# shoff400.net
KiCad netlist of a schematic drawn in EAGLE
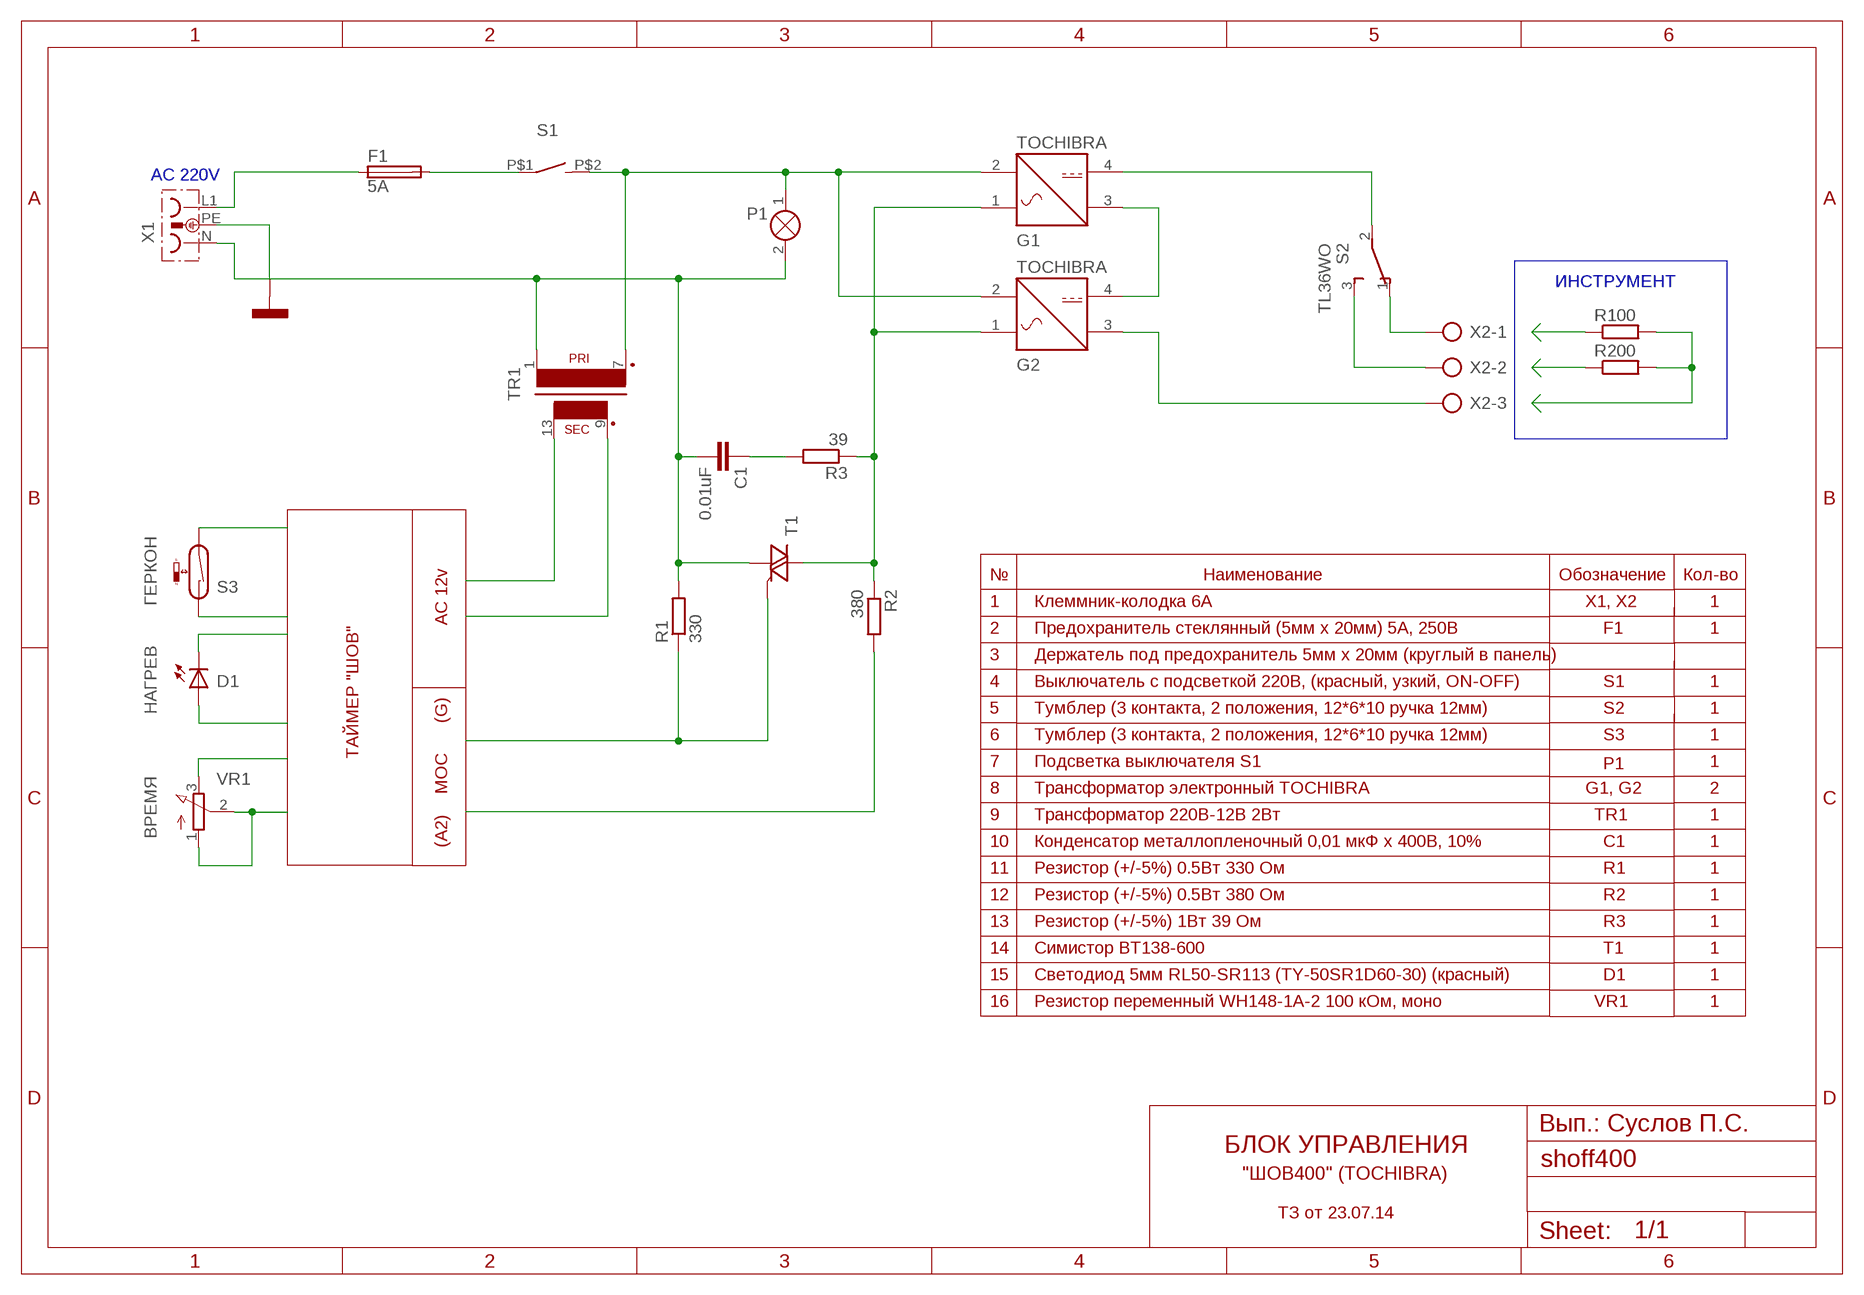
[diagram p0: schematic, sheet 1]

(export (version "E")
  (design (tool "Eeschema 10.0.6"))
  (components
    (comp (ref "C1")
      (value "0.01uF")
      (footprint "eagle-import:C025-030X050")
      (libsource (lib "eagle-import") (part "C-EU025-030X050"))
    )
    (comp (ref "F1")
      (value "5A")
      (footprint "eagle-import:GSH15")
      (fields (field (name "MPN") "64900001039"))
      (libsource (lib "eagle-import") (part "GSH15"))
    )
    (comp (ref "G1")
      (value "TOCHIBRA")
      (footprint "eagle-import:NETZTEIL_GLEICHSPANNUNG")
      (libsource (lib "eagle-import") (part "NETZTEIL_GLEICHSPANNUNG"))
    )
    (comp (ref "G2")
      (value "TOCHIBRA")
      (footprint "eagle-import:NETZTEIL_GLEICHSPANNUNG")
      (libsource (lib "eagle-import") (part "NETZTEIL_GLEICHSPANNUNG"))
    )
    (comp (ref "GG")
      (value "MASSE_ALLGEMEIN")
      (footprint "eagle-import:MASSE_ALLGEMEIN")
      (libsource (lib "eagle-import") (part "MASSE_ALLGEMEIN"))
    )
    (comp (ref "P1")
      (value "SIGNALLAMPE")
      (footprint "eagle-import:LAMPE")
      (libsource (lib "eagle-import") (part "SIGNALLAMPE"))
    )
    (comp (ref "R1")
      (value "330")
      (footprint "eagle-import:0207_5V")
      (libsource (lib "eagle-import") (part "R-EU_0207/5V"))
    )
    (comp (ref "R2")
      (value "380")
      (footprint "eagle-import:0207_5V")
      (libsource (lib "eagle-import") (part "R-EU_0207/5V"))
    )
    (comp (ref "R3")
      (value "39")
      (footprint "eagle-import:0207_5V")
      (libsource (lib "eagle-import") (part "R-EU_0207/5V"))
    )
    (comp (ref "R100")
      (value "R-EU_R0201")
      (footprint "eagle-import:R0201")
      (libsource (lib "eagle-import") (part "R-EU_R0201"))
    )
    (comp (ref "R200")
      (value "R-EU_R0201")
      (footprint "eagle-import:R0201")
      (libsource (lib "eagle-import") (part "R-EU_R0201"))
    )
    (comp (ref "S1")
      (value "SCHLIESSER_ARBEITSKONTAKT")
      (footprint "eagle-import:1")
      (libsource (lib "eagle-import") (part "SCHLIESSER_ARBEITSKONTAKT"))
    )
    (comp (ref "S2")
      (value "TL36WO")
      (footprint "eagle-import:TL3XWO")
      (libsource (lib "eagle-import") (part "TL36WO"))
    )
    (comp (ref "S3")
      (value "ГЕРКОН")
      (footprint "eagle-import:CT10-G1")
      (fields (field (name "MF") "COTO TECHNOLOGY") (field (name "MPN") "CT10-1530-G1"))
      (libsource (lib "eagle-import") (part "REED-SWITCH-CT10-1530-G1"))
    )
    (comp (ref "T1")
      (value "BTA26-V")
      (footprint "eagle-import:TOP3S-1")
      (libsource (lib "eagle-import") (part "BTA26-V"))
    )
    (comp (ref "TR1")
      (value "BV054-5381.0K")
      (footprint "eagle-import:EI54-18,8_16VA")
      (libsource (lib "eagle-import") (part "BV054-5381.0K"))
    )
    (comp (ref "X1")
      (value "STECKDOSE")
      (footprint "eagle-import:STECKDOSE")
      (libsource (lib "eagle-import") (part "STECKDOSE"))
    )
    (comp (ref "X2")
      (value "AK500/3")
      (footprint "eagle-import:AK500_3")
      (libsource (lib "eagle-import") (part "AK500/3"))
    )
    (comp (ref "ВРЕМЯ")
      (value "3RP/1610N")
      (footprint "eagle-import:3RP_1610N")
      (libsource (lib "eagle-import") (part "3RP/1610N"))
    )
    (comp (ref "ГОТОВ")
      (value "НАГРЕВ")
      (footprint "eagle-import:LED5MM")
      (libsource (lib "eagle-import") (part "LED5MM"))
    )
  )
  (nets
    (net (code "1") (name "Net-(C1-Pad1)") (class "Default")
      (node (ref "C1") (pin "1") (pinfunction "1_1") (pintype "passive"))
      (node (ref "R3") (pin "2") (pinfunction "2_2") (pintype "passive"))
    )
    (net (code "2") (name "Net-(F1-Pad1)") (class "Default")
      (node (ref "F1") (pin "1") (pinfunction "1_1") (pintype "passive"))
      (node (ref "X1") (pin "L1") (pinfunction "L1_L1") (pintype "passive"))
    )
    (net (code "3") (name "Net-(G1-Pad1)") (class "Default")
      (node (ref "G1") (pin "1") (pinfunction "1_1") (pintype "passive"))
      (node (ref "G2") (pin "1") (pinfunction "1_1") (pintype "passive"))
      (node (ref "R2") (pin "1") (pinfunction "1_1") (pintype "passive"))
      (node (ref "R3") (pin "1") (pinfunction "1_1") (pintype "passive"))
      (node (ref "T1") (pin "A2") (pinfunction "A2_A2") (pintype "passive"))
    )
    (net (code "4") (name "Net-(G1-Pad3)") (class "Default")
      (node (ref "G1") (pin "3") (pinfunction "3_3") (pintype "passive"))
      (node (ref "G2") (pin "4") (pinfunction "4_4") (pintype "passive"))
    )
    (net (code "5") (name "Net-(GG-0V)") (class "Default")
      (node (ref "GG") (pin "1") (pinfunction "0V_1") (pintype "passive"))
      (node (ref "X1") (pin "PE") (pinfunction "PE_PE") (pintype "passive"))
    )
    (net (code "6") (name "Net-(P1-X1)") (class "Default")
      (node (ref "G1") (pin "2") (pinfunction "2_2") (pintype "passive"))
      (node (ref "G2") (pin "2") (pinfunction "2_2") (pintype "passive"))
      (node (ref "P1") (pin "1") (pinfunction "X1_1") (pintype "passive"))
      (node (ref "S1") (pin "P$2") (pinfunction "3_P$2") (pintype "passive"))
      (node (ref "TR1") (pin "7") (pinfunction "P2_7") (pintype "passive"))
    )
    (net (code "7") (name "Net-(P1-X2)") (class "Default")
      (node (ref "C1") (pin "2") (pinfunction "2_2") (pintype "passive"))
      (node (ref "P1") (pin "2") (pinfunction "X2_2") (pintype "passive"))
      (node (ref "R1") (pin "2") (pinfunction "2_2") (pintype "passive"))
      (node (ref "T1") (pin "A1") (pinfunction "A1_A1") (pintype "passive"))
      (node (ref "TR1") (pin "1") (pinfunction "P1_1") (pintype "passive"))
      (node (ref "X1") (pin "N") (pinfunction "N_N") (pintype "passive"))
    )
    (net (code "8") (name "Net-(R1-Pad1)") (class "Default")
      (node (ref "R1") (pin "1") (pinfunction "1_1") (pintype "passive"))
      (node (ref "T1") (pin "G") (pinfunction "G_G") (pintype "passive"))
    )
    (net (code "9") (name "Net-(R100-Pad2)") (class "Default")
      (node (ref "R100") (pin "2") (pinfunction "2_2") (pintype "passive"))
      (node (ref "R200") (pin "2") (pinfunction "2_2") (pintype "passive"))
    )
    (net (code "10") (name "Net-(S1-4)") (class "Default")
      (node (ref "F1") (pin "2") (pinfunction "2_2") (pintype "passive"))
      (node (ref "S1") (pin "P$1") (pinfunction "4_P$1") (pintype "passive"))
    )
    (net (code "11") (name "Net-(S2-O)") (class "Default")
      (node (ref "S2") (pin "1") (pinfunction "O_1") (pintype "passive"))
      (node (ref "X2") (pin "1") (pinfunction "KL_1") (pintype "passive"))
    )
    (net (code "12") (name "Net-(S2-P)") (class "Default")
      (node (ref "G1") (pin "4") (pinfunction "4_4") (pintype "passive"))
      (node (ref "S2") (pin "2") (pinfunction "P_2") (pintype "passive"))
    )
    (net (code "13") (name "Net-(S2-S)") (class "Default")
      (node (ref "S2") (pin "3") (pinfunction "S_3") (pintype "passive"))
      (node (ref "X2") (pin "2") (pinfunction "KL_2") (pintype "passive"))
    )
    (net (code "14") (name "Net-(X2C-KL)") (class "Default")
      (node (ref "G2") (pin "3") (pinfunction "3_3") (pintype "passive"))
      (node (ref "X2") (pin "3") (pinfunction "KL_3") (pintype "passive"))
    )
    (net (code "15") (name "Net-(ВРЕМЯ-A)") (class "Default")
      (node (ref "ВРЕМЯ") (pin "1") (pinfunction "A_1") (pintype "passive"))
      (node (ref "ВРЕМЯ") (pin "2") (pinfunction "S_2") (pintype "passive"))
    )
    (net (code "16") (name "unconnected-(R2-Pad2)") (class "Default")
      (node (ref "R2") (pin "2") (pinfunction "2_2") (pintype "passive"))
    )
    (net (code "17") (name "unconnected-(R100-Pad1)") (class "Default")
      (node (ref "R100") (pin "1") (pinfunction "1_1") (pintype "passive"))
    )
    (net (code "18") (name "unconnected-(R200-Pad1)") (class "Default")
      (node (ref "R200") (pin "1") (pinfunction "1_1") (pintype "passive"))
    )
    (net (code "19") (name "unconnected-(S3-Pad1)") (class "Default")
      (node (ref "S3") (pin "1") (pinfunction "1_1") (pintype "passive"))
    )
    (net (code "20") (name "unconnected-(S3-Pad2)") (class "Default")
      (node (ref "S3") (pin "2") (pinfunction "2_2") (pintype "passive"))
    )
    (net (code "21") (name "unconnected-(TR1-S3-Pad9)") (class "Default")
      (node (ref "TR1") (pin "9") (pinfunction "S3_9") (pintype "passive"))
    )
    (net (code "22") (name "unconnected-(TR1-S4-Pad13)") (class "Default")
      (node (ref "TR1") (pin "13") (pinfunction "S4_13") (pintype "passive"))
    )
    (net (code "23") (name "unconnected-(ВРЕМЯ-E-Pad3)") (class "Default")
      (node (ref "ВРЕМЯ") (pin "3") (pinfunction "E_3") (pintype "passive"))
    )
    (net (code "24") (name "unconnected-(ГОТОВ-C-PadK)") (class "Default")
      (node (ref "ГОТОВ") (pin "K") (pinfunction "C_K") (pintype "passive"))
    )
    (net (code "25") (name "unconnected-(ГОТОВ-PadA)") (class "Default")
      (node (ref "ГОТОВ") (pin "A") (pinfunction "A_A") (pintype "passive"))
    )
  )
)
